# iwing-mrf_shield8.net
KiCad netlist of a schematic drawn in EAGLE
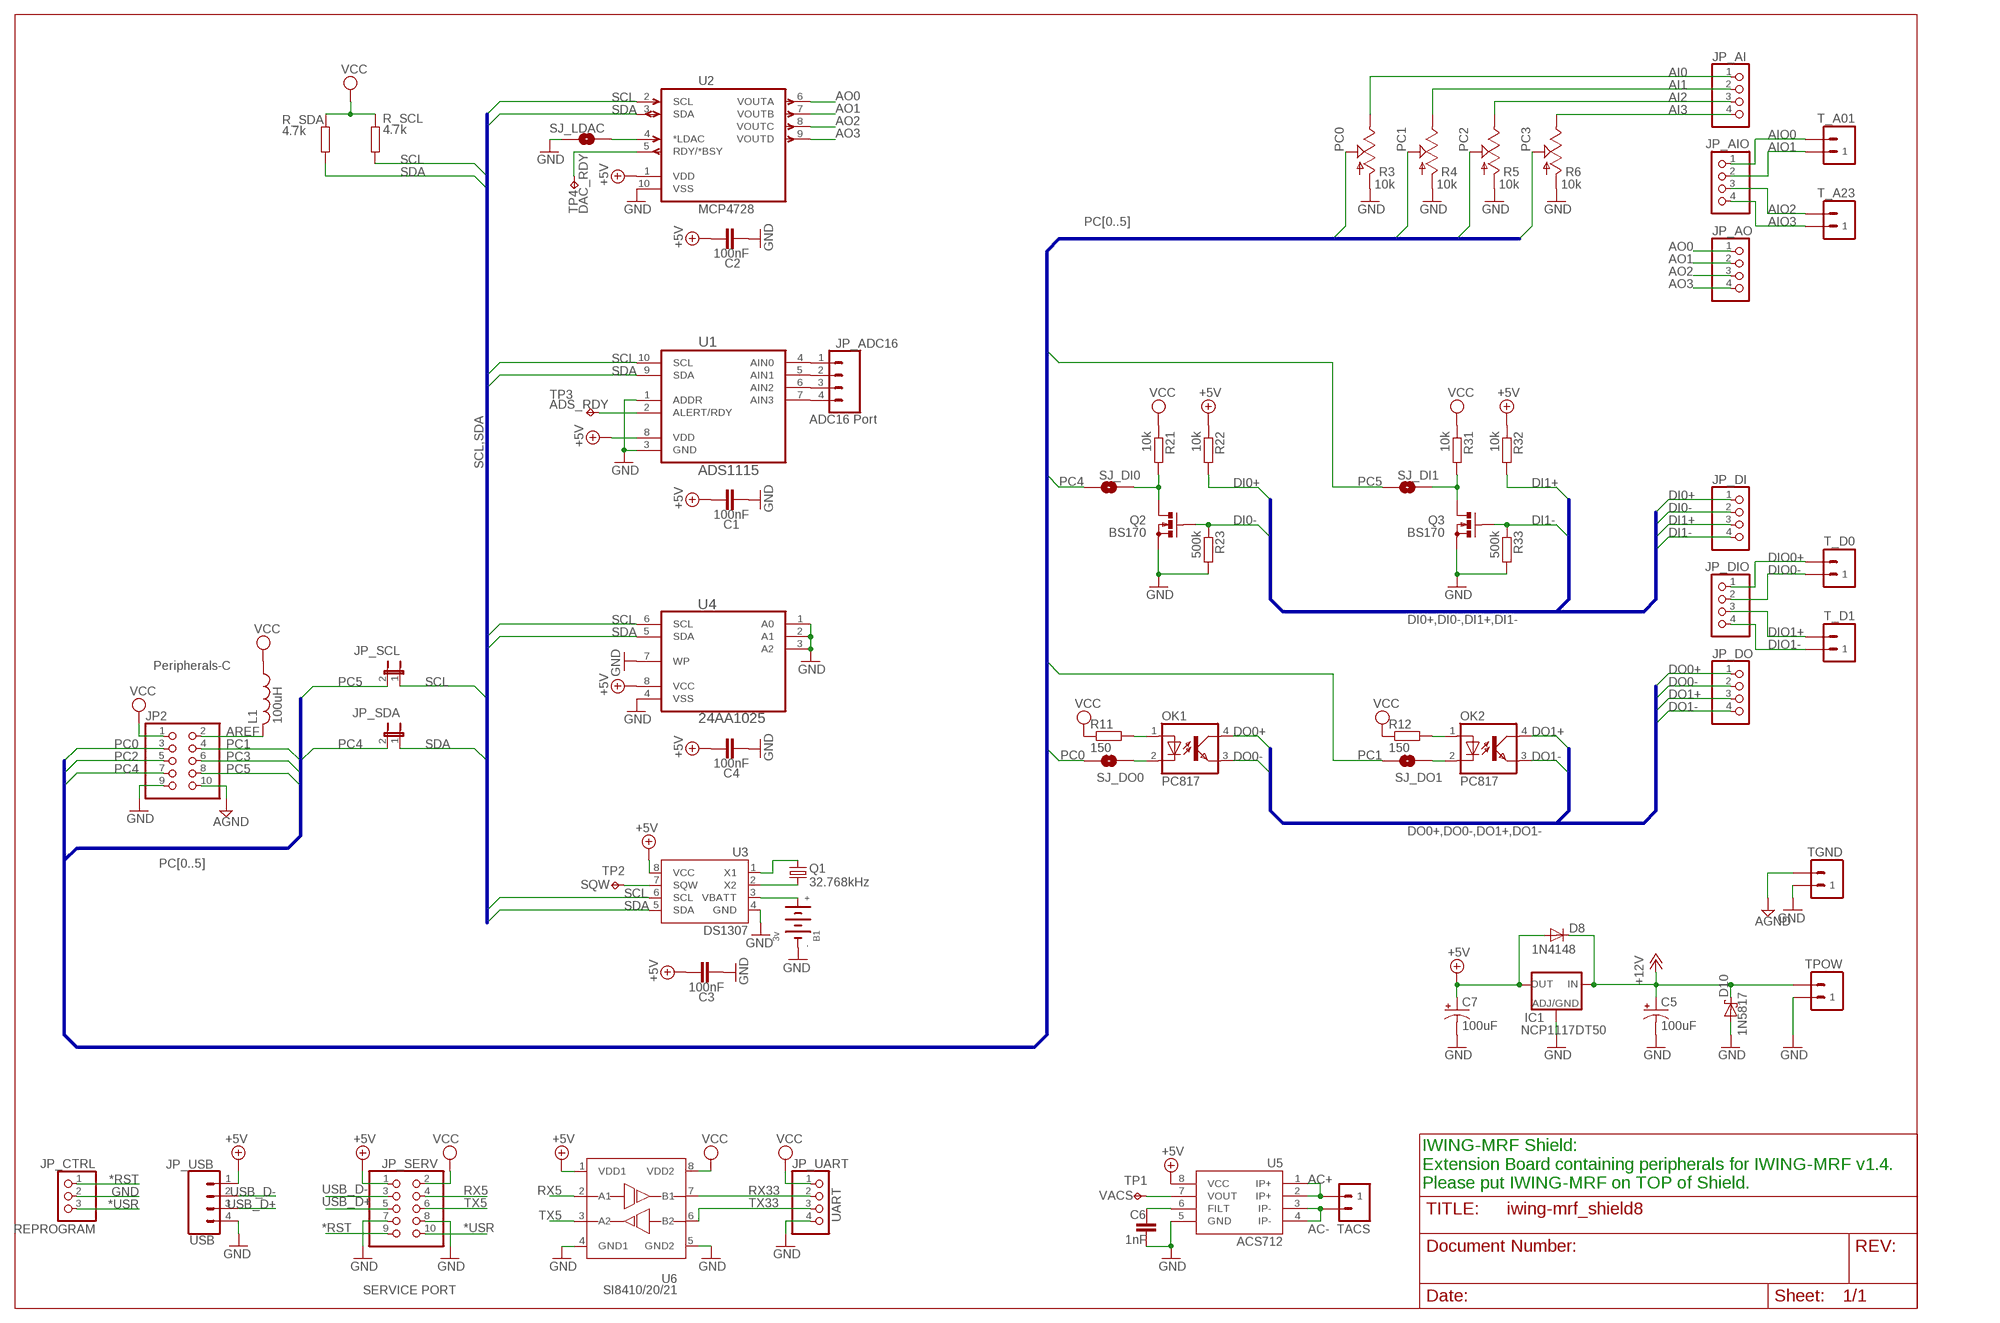
[diagram p0: schematic, sheet 1]

(export (version "E")
  (design (tool "Eeschema 10.0.6"))
  (components
    (comp (ref "B1")
      (value "3v")
      (footprint "eagle-import:CR2032")
      (libsource (lib "eagle-import") (part "BATTERYCR2032"))
    )
    (comp (ref "C1")
      (value "100nF")
      (footprint "eagle-import:RCL_C050-025X075")
      (libsource (lib "eagle-import") (part "RCL_C-EU050-025X075"))
    )
    (comp (ref "C2")
      (value "100nF")
      (footprint "eagle-import:RCL_C050-025X075")
      (libsource (lib "eagle-import") (part "RCL_C-EU050-025X075"))
    )
    (comp (ref "C3")
      (value "100nF")
      (footprint "eagle-import:RCL_C050-025X075")
      (libsource (lib "eagle-import") (part "RCL_C-EU050-025X075"))
    )
    (comp (ref "C4")
      (value "100nF")
      (footprint "eagle-import:RCL_C050-025X075")
      (libsource (lib "eagle-import") (part "RCL_C-EU050-025X075"))
    )
    (comp (ref "C5")
      (value "100uF")
      (footprint "eagle-import:RCL_E2,5-7")
      (libsource (lib "eagle-import") (part "RCL_CPOL-USE2.5-7"))
    )
    (comp (ref "C6")
      (value "1nF")
      (footprint "eagle-import:RCL_C050-025X075")
      (libsource (lib "eagle-import") (part "RCL_C-EU050-025X075"))
    )
    (comp (ref "C7")
      (value "100uF")
      (footprint "eagle-import:RCL_E2,5-7")
      (libsource (lib "eagle-import") (part "RCL_CPOL-USE2.5-7"))
    )
    (comp (ref "D8")
      (value "1N4148")
      (footprint "eagle-import:DO35-100V")
      (libsource (lib "eagle-import") (part "1N4148-V"))
    )
    (comp (ref "D10")
      (value "1N5817")
      (footprint "eagle-import:DO41-150V")
      (libsource (lib "eagle-import") (part "1N5819-V"))
    )
    (comp (ref "IC1")
      (value "NCP1117DT50")
      (footprint "eagle-import:DPACK")
      (libsource (lib "eagle-import") (part "NCP1117?DT50"))
    )
    (comp (ref "JP2")
      (value "HEADER-2X5")
      (footprint "eagle-import:2X05")
      (libsource (lib "eagle-import") (part "HEADER-2X5"))
    )
    (comp (ref "JP_ADC16")
      (value "ADC16 Port")
      (footprint "eagle-import:1X04")
      (libsource (lib "eagle-import") (part "M04PTH"))
    )
    (comp (ref "JP_AI")
      (value "HEADER-1X4ROUND")
      (footprint "eagle-import:1X04_ROUND")
      (libsource (lib "eagle-import") (part "HEADER-1X4ROUND"))
    )
    (comp (ref "JP_AIO")
      (value "HEADER-1X4ROUND")
      (footprint "eagle-import:1X04_ROUND")
      (libsource (lib "eagle-import") (part "HEADER-1X4ROUND"))
    )
    (comp (ref "JP_AO")
      (value "HEADER-1X4ROUND")
      (footprint "eagle-import:1X04_ROUND")
      (libsource (lib "eagle-import") (part "HEADER-1X4ROUND"))
    )
    (comp (ref "JP_CTRL")
      (value "REPROGRAM")
      (footprint "eagle-import:1X03")
      (libsource (lib "eagle-import") (part "PINHD-1X3"))
    )
    (comp (ref "JP_DI")
      (value "HEADER-1X4ROUND")
      (footprint "eagle-import:1X04_ROUND")
      (libsource (lib "eagle-import") (part "HEADER-1X4ROUND"))
    )
    (comp (ref "JP_DIO")
      (value "HEADER-1X4ROUND")
      (footprint "eagle-import:1X04_ROUND")
      (libsource (lib "eagle-import") (part "HEADER-1X4ROUND"))
    )
    (comp (ref "JP_DO")
      (value "HEADER-1X4ROUND")
      (footprint "eagle-import:1X04_ROUND")
      (libsource (lib "eagle-import") (part "HEADER-1X4ROUND"))
    )
    (comp (ref "JP_SCL")
      (value "JUMPER-2SMD-NO")
      (footprint "eagle-import:SJ_2S-NO")
      (libsource (lib "eagle-import") (part "JUMPER-2SMD-NO"))
    )
    (comp (ref "JP_SDA")
      (value "JUMPER-2SMD-NO")
      (footprint "eagle-import:SJ_2S-NO")
      (libsource (lib "eagle-import") (part "JUMPER-2SMD-NO"))
    )
    (comp (ref "JP_SERV")
      (value "SERVICE PORT")
      (footprint "eagle-import:2X05")
      (libsource (lib "eagle-import") (part "HEADER-2X5"))
    )
    (comp (ref "JP_UART")
      (value "HEADER-1X4ROUND")
      (footprint "eagle-import:1X04_ROUND")
      (libsource (lib "eagle-import") (part "HEADER-1X4ROUND"))
    )
    (comp (ref "JP_USB")
      (value "USB")
      (footprint "eagle-import:1X04")
      (libsource (lib "eagle-import") (part "M04PTH"))
    )
    (comp (ref "L1")
      (value "100uH")
      (footprint "eagle-import:0204_5")
      (libsource (lib "eagle-import") (part "L-US0204/5"))
    )
    (comp (ref "OK1")
      (value "PC817")
      (footprint "eagle-import:DIL04")
      (fields (field (name "MPN") "PC817X4J000F"))
      (libsource (lib "eagle-import") (part "PC817"))
    )
    (comp (ref "OK2")
      (value "PC817")
      (footprint "eagle-import:DIL04")
      (fields (field (name "MPN") "PC817X4J000F"))
      (libsource (lib "eagle-import") (part "PC817"))
    )
    (comp (ref "Q1")
      (value "32.768kHz")
      (footprint "eagle-import:CRYSTAL_TC26H")
      (libsource (lib "eagle-import") (part "CRYSTAL_CRYSTALTC26H"))
    )
    (comp (ref "Q2")
      (value "BS170")
      (footprint "eagle-import:TO92-")
      (libsource (lib "eagle-import") (part "BS170"))
    )
    (comp (ref "Q3")
      (value "BS170")
      (footprint "eagle-import:TO92-")
      (libsource (lib "eagle-import") (part "BS170"))
    )
    (comp (ref "R3")
      (value "10k")
      (footprint "eagle-import:B64Y")
      (libsource (lib "eagle-import") (part "TRIM_US-B64Y"))
    )
    (comp (ref "R4")
      (value "10k")
      (footprint "eagle-import:B64Y")
      (libsource (lib "eagle-import") (part "TRIM_US-B64Y"))
    )
    (comp (ref "R5")
      (value "10k")
      (footprint "eagle-import:B64Y")
      (libsource (lib "eagle-import") (part "TRIM_US-B64Y"))
    )
    (comp (ref "R6")
      (value "10k")
      (footprint "eagle-import:B64Y")
      (libsource (lib "eagle-import") (part "TRIM_US-B64Y"))
    )
    (comp (ref "R11")
      (value "150")
      (footprint "eagle-import:0204_5")
      (libsource (lib "eagle-import") (part "R-EU_0204/5"))
    )
    (comp (ref "R12")
      (value "150")
      (footprint "eagle-import:0204_5")
      (libsource (lib "eagle-import") (part "R-EU_0204/5"))
    )
    (comp (ref "R21")
      (value "10k")
      (footprint "eagle-import:0204_5")
      (libsource (lib "eagle-import") (part "R-EU_0204/5"))
    )
    (comp (ref "R22")
      (value "10k")
      (footprint "eagle-import:0204_5")
      (libsource (lib "eagle-import") (part "R-EU_0204/5"))
    )
    (comp (ref "R23")
      (value "500k")
      (footprint "eagle-import:0204_5")
      (libsource (lib "eagle-import") (part "R-EU_0204/5"))
    )
    (comp (ref "R31")
      (value "10k")
      (footprint "eagle-import:0204_5")
      (libsource (lib "eagle-import") (part "R-EU_0204/5"))
    )
    (comp (ref "R32")
      (value "10k")
      (footprint "eagle-import:0204_5")
      (libsource (lib "eagle-import") (part "R-EU_0204/5"))
    )
    (comp (ref "R33")
      (value "500k")
      (footprint "eagle-import:0204_5")
      (libsource (lib "eagle-import") (part "R-EU_0204/5"))
    )
    (comp (ref "R_SCL")
      (value "4.7k")
      (footprint "eagle-import:0204_5")
      (libsource (lib "eagle-import") (part "R-EU_0204/5"))
    )
    (comp (ref "R_SDA")
      (value "4.7k")
      (footprint "eagle-import:0204_5")
      (libsource (lib "eagle-import") (part "R-EU_0204/5"))
    )
    (comp (ref "SJ_DI0")
      (value "SOLDERJUMPERNO")
      (footprint "eagle-import:SJ_2S-NO")
      (libsource (lib "eagle-import") (part "SOLDERJUMPERNO"))
    )
    (comp (ref "SJ_DI1")
      (value "SOLDERJUMPERNO")
      (footprint "eagle-import:SJ_2S-NO")
      (libsource (lib "eagle-import") (part "SOLDERJUMPERNO"))
    )
    (comp (ref "SJ_DO0")
      (value "SOLDERJUMPERNO")
      (footprint "eagle-import:SJ_2S-NO")
      (libsource (lib "eagle-import") (part "SOLDERJUMPERNO"))
    )
    (comp (ref "SJ_DO1")
      (value "SOLDERJUMPERNO")
      (footprint "eagle-import:SJ_2S-NO")
      (libsource (lib "eagle-import") (part "SOLDERJUMPERNO"))
    )
    (comp (ref "SJ_LDAC")
      (value "SOLDERJUMPERNO")
      (footprint "eagle-import:SJ_2S-NO")
      (libsource (lib "eagle-import") (part "SOLDERJUMPERNO"))
    )
    (comp (ref "TACS")
      (value "ST02-DT-126")
      (footprint "eagle-import:DT-126VP-2P")
      (libsource (lib "eagle-import") (part "ST02-DT-126"))
    )
    (comp (ref "TGND")
      (value "ST02-5MM")
      (footprint "eagle-import:EK500V-02P")
      (libsource (lib "eagle-import") (part "ST02-5MM"))
    )
    (comp (ref "TP1")
      (value "TPPAD1-13")
      (footprint "eagle-import:P1-13")
      (fields (field (name "TP_SIGNAL_NAME") "VACS"))
      (libsource (lib "eagle-import") (part "TPPAD1-13"))
    )
    (comp (ref "TP2")
      (value "TPPAD1-13")
      (footprint "eagle-import:P1-13")
      (fields (field (name "TP_SIGNAL_NAME") "SQW"))
      (libsource (lib "eagle-import") (part "TPPAD1-13"))
    )
    (comp (ref "TP3")
      (value "TPB1,27")
      (footprint "eagle-import:B1,27")
      (fields (field (name "TP_SIGNAL_NAME") "ADS_RDY"))
      (libsource (lib "eagle-import") (part "TPB1,27"))
    )
    (comp (ref "TP4")
      (value "TPPAD1-13")
      (footprint "eagle-import:P1-13")
      (fields (field (name "TP_SIGNAL_NAME") "DAC_RDY"))
      (libsource (lib "eagle-import") (part "TPPAD1-13"))
    )
    (comp (ref "TPOW")
      (value "ST02-5MM")
      (footprint "eagle-import:EK500V-02P")
      (libsource (lib "eagle-import") (part "ST02-5MM"))
    )
    (comp (ref "T_A01")
      (value "ST02-5MM")
      (footprint "eagle-import:EK500V-02P")
      (libsource (lib "eagle-import") (part "ST02-5MM"))
    )
    (comp (ref "T_A23")
      (value "ST02-5MM")
      (footprint "eagle-import:EK500V-02P")
      (libsource (lib "eagle-import") (part "ST02-5MM"))
    )
    (comp (ref "T_D0")
      (value "ST02-5MM")
      (footprint "eagle-import:EK500V-02P")
      (libsource (lib "eagle-import") (part "ST02-5MM"))
    )
    (comp (ref "T_D1")
      (value "ST02-5MM")
      (footprint "eagle-import:EK500V-02P")
      (libsource (lib "eagle-import") (part "ST02-5MM"))
    )
    (comp (ref "U1")
      (value "ADS1115")
      (footprint "eagle-import:MSOP-10")
      (libsource (lib "eagle-import") (part "ADS1115IDGST"))
    )
    (comp (ref "U2")
      (value "MCP4728")
      (footprint "eagle-import:MSOP-10")
      (libsource (lib "eagle-import") (part "MCP4728-E/UN"))
    )
    (comp (ref "U3")
      (value "DS1307")
      (footprint "eagle-import:DIL08")
      (libsource (lib "eagle-import") (part "DS1307D08"))
    )
    (comp (ref "U4")
      (value "24AA1025")
      (footprint "eagle-import:DIL08")
      (libsource (lib "eagle-import") (part "24AA1025-I/P"))
    )
    (comp (ref "U5")
      (value "ACS712")
      (footprint "eagle-import:SO08")
      (libsource (lib "eagle-import") (part "ACS712"))
    )
    (comp (ref "U6")
      (value "SI8410/20/21")
      (footprint "eagle-import:SO-08")
      (libsource (lib "eagle-import") (part "SI8410/20/21"))
    )
  )
  (nets
    (net (code "1") (name "+5V") (class "Default")
      (node (ref "C1") (pin "1") (pinfunction "1_1") (pintype "passive"))
      (node (ref "C2") (pin "1") (pinfunction "1_1") (pintype "passive"))
      (node (ref "C3") (pin "1") (pinfunction "1_1") (pintype "passive"))
      (node (ref "C4") (pin "1") (pinfunction "1_1") (pintype "passive"))
      (node (ref "C7") (pin "+") (pinfunction "+_+") (pintype "passive"))
      (node (ref "D8") (pin "A") (pinfunction "A_A") (pintype "passive"))
      (node (ref "IC1") (pin "4") (pinfunction "OUT_4") (pintype "passive"))
      (node (ref "JP_SERV") (pin "1") (pinfunction "1_1") (pintype "passive"))
      (node (ref "JP_USB") (pin "1") (pinfunction "1_1") (pintype "passive"))
      (node (ref "R22") (pin "1") (pinfunction "1_1") (pintype "passive"))
      (node (ref "R32") (pin "1") (pinfunction "1_1") (pintype "passive"))
      (node (ref "U1") (pin "8") (pinfunction "VDD_8") (pintype "power_in"))
      (node (ref "U2") (pin "1") (pinfunction "VDD_1") (pintype "power_in"))
      (node (ref "U3") (pin "8") (pinfunction "VCC_8") (pintype "bidirectional"))
      (node (ref "U4") (pin "8") (pinfunction "VCC_8") (pintype "power_in"))
      (node (ref "U5") (pin "8") (pinfunction "VCC_8") (pintype "bidirectional"))
      (node (ref "U6") (pin "1") (pinfunction "VDD1_1") (pintype "power_in"))
    )
    (net (code "2") (name "+12V") (class "Default")
      (node (ref "C5") (pin "+") (pinfunction "+_+") (pintype "passive"))
      (node (ref "D10") (pin "C") (pinfunction "C_C") (pintype "passive"))
      (node (ref "D8") (pin "C") (pinfunction "C_C") (pintype "passive"))
      (node (ref "IC1") (pin "3") (pinfunction "IN_3") (pintype "input"))
      (node (ref "TPOW") (pin "P$2") (pinfunction "2_P$2") (pintype "passive"))
    )
    (net (code "3") (name "/*RST") (class "Default")
      (node (ref "JP_CTRL") (pin "1") (pinfunction "1_1") (pintype "passive"))
      (node (ref "JP_SERV") (pin "9") (pinfunction "9_9") (pintype "passive"))
    )
    (net (code "4") (name "/*USR") (class "Default")
      (node (ref "JP_CTRL") (pin "3") (pinfunction "3_3") (pintype "passive"))
      (node (ref "JP_SERV") (pin "10") (pinfunction "10_10") (pintype "passive"))
    )
    (net (code "5") (name "/AC+") (class "Default")
      (node (ref "TACS") (pin "P$1") (pinfunction "1_P$1") (pintype "passive"))
      (node (ref "U5") (pin "1") (pinfunction "IP+_1") (pintype "bidirectional"))
      (node (ref "U5") (pin "2") (pinfunction "IP+_2") (pintype "bidirectional"))
    )
    (net (code "6") (name "/AC-") (class "Default")
      (node (ref "TACS") (pin "P$2") (pinfunction "2_P$2") (pintype "passive"))
      (node (ref "U5") (pin "3") (pinfunction "IP-_3") (pintype "bidirectional"))
      (node (ref "U5") (pin "4") (pinfunction "IP-_4") (pintype "bidirectional"))
    )
    (net (code "7") (name "/AI0") (class "Default")
      (node (ref "JP_AI") (pin "1") (pinfunction "1_1") (pintype "passive"))
      (node (ref "R3") (pin "E") (pinfunction "E_E") (pintype "passive"))
    )
    (net (code "8") (name "/AI1") (class "Default")
      (node (ref "JP_AI") (pin "2") (pinfunction "2_2") (pintype "passive"))
      (node (ref "R4") (pin "E") (pinfunction "E_E") (pintype "passive"))
    )
    (net (code "9") (name "/AI2") (class "Default")
      (node (ref "JP_AI") (pin "3") (pinfunction "3_3") (pintype "passive"))
      (node (ref "R5") (pin "E") (pinfunction "E_E") (pintype "passive"))
    )
    (net (code "10") (name "/AI3") (class "Default")
      (node (ref "JP_AI") (pin "4") (pinfunction "4_4") (pintype "passive"))
      (node (ref "R6") (pin "E") (pinfunction "E_E") (pintype "passive"))
    )
    (net (code "11") (name "/AIO0") (class "Default")
      (node (ref "JP_AIO") (pin "1") (pinfunction "1_1") (pintype "passive"))
      (node (ref "T_A01") (pin "P$2") (pinfunction "2_P$2") (pintype "passive"))
    )
    (net (code "12") (name "/AIO1") (class "Default")
      (node (ref "JP_AIO") (pin "2") (pinfunction "2_2") (pintype "passive"))
      (node (ref "T_A01") (pin "P$1") (pinfunction "1_P$1") (pintype "passive"))
    )
    (net (code "13") (name "/AIO2") (class "Default")
      (node (ref "JP_AIO") (pin "3") (pinfunction "3_3") (pintype "passive"))
      (node (ref "T_A23") (pin "P$2") (pinfunction "2_P$2") (pintype "passive"))
    )
    (net (code "14") (name "/AIO3") (class "Default")
      (node (ref "JP_AIO") (pin "4") (pinfunction "4_4") (pintype "passive"))
      (node (ref "T_A23") (pin "P$1") (pinfunction "1_P$1") (pintype "passive"))
    )
    (net (code "15") (name "/AO0") (class "Default")
      (node (ref "JP_AO") (pin "1") (pinfunction "1_1") (pintype "passive"))
      (node (ref "U2") (pin "6") (pinfunction "VOUTA_6") (pintype "output"))
    )
    (net (code "16") (name "/AO1") (class "Default")
      (node (ref "JP_AO") (pin "2") (pinfunction "2_2") (pintype "passive"))
      (node (ref "U2") (pin "7") (pinfunction "VOUTB_7") (pintype "output"))
    )
    (net (code "17") (name "/AO2") (class "Default")
      (node (ref "JP_AO") (pin "3") (pinfunction "3_3") (pintype "passive"))
      (node (ref "U2") (pin "8") (pinfunction "VOUTC_8") (pintype "output"))
    )
    (net (code "18") (name "/AO3") (class "Default")
      (node (ref "JP_AO") (pin "4") (pinfunction "4_4") (pintype "passive"))
      (node (ref "U2") (pin "9") (pinfunction "VOUTD_9") (pintype "output"))
    )
    (net (code "19") (name "/AREF") (class "Default")
      (node (ref "JP2") (pin "2") (pinfunction "2_2") (pintype "passive"))
      (node (ref "L1") (pin "2") (pinfunction "2_2") (pintype "passive"))
    )
    (net (code "20") (name "/DI0+") (class "Default")
      (node (ref "JP_DI") (pin "1") (pinfunction "1_1") (pintype "passive"))
      (node (ref "R22") (pin "2") (pinfunction "2_2") (pintype "passive"))
    )
    (net (code "21") (name "/DI0-") (class "Default")
      (node (ref "JP_DI") (pin "2") (pinfunction "2_2") (pintype "passive"))
      (node (ref "Q2") (pin "2") (pinfunction "G_2") (pintype "passive"))
      (node (ref "R23") (pin "1") (pinfunction "1_1") (pintype "passive"))
    )
    (net (code "22") (name "/DI1+") (class "Default")
      (node (ref "JP_DI") (pin "3") (pinfunction "3_3") (pintype "passive"))
      (node (ref "R32") (pin "2") (pinfunction "2_2") (pintype "passive"))
    )
    (net (code "23") (name "/DI1-") (class "Default")
      (node (ref "JP_DI") (pin "4") (pinfunction "4_4") (pintype "passive"))
      (node (ref "Q3") (pin "2") (pinfunction "G_2") (pintype "passive"))
      (node (ref "R33") (pin "1") (pinfunction "1_1") (pintype "passive"))
    )
    (net (code "24") (name "/DIO0+") (class "Default")
      (node (ref "JP_DIO") (pin "1") (pinfunction "1_1") (pintype "passive"))
      (node (ref "T_D0") (pin "P$2") (pinfunction "2_P$2") (pintype "passive"))
    )
    (net (code "25") (name "/DIO0-") (class "Default")
      (node (ref "JP_DIO") (pin "2") (pinfunction "2_2") (pintype "passive"))
      (node (ref "T_D0") (pin "P$1") (pinfunction "1_P$1") (pintype "passive"))
    )
    (net (code "26") (name "/DIO1+") (class "Default")
      (node (ref "JP_DIO") (pin "3") (pinfunction "3_3") (pintype "passive"))
      (node (ref "T_D1") (pin "P$2") (pinfunction "2_P$2") (pintype "passive"))
    )
    (net (code "27") (name "/DIO1-") (class "Default")
      (node (ref "JP_DIO") (pin "4") (pinfunction "4_4") (pintype "passive"))
      (node (ref "T_D1") (pin "P$1") (pinfunction "1_P$1") (pintype "passive"))
    )
    (net (code "28") (name "/DO0+") (class "Default")
      (node (ref "JP_DO") (pin "1") (pinfunction "1_1") (pintype "passive"))
      (node (ref "OK1") (pin "4") (pinfunction "COL_4") (pintype "passive"))
    )
    (net (code "29") (name "/DO0-") (class "Default")
      (node (ref "JP_DO") (pin "2") (pinfunction "2_2") (pintype "passive"))
      (node (ref "OK1") (pin "3") (pinfunction "EMIT_3") (pintype "passive"))
    )
    (net (code "30") (name "/DO1+") (class "Default")
      (node (ref "JP_DO") (pin "3") (pinfunction "3_3") (pintype "passive"))
      (node (ref "OK2") (pin "4") (pinfunction "COL_4") (pintype "passive"))
    )
    (net (code "31") (name "/DO1-") (class "Default")
      (node (ref "JP_DO") (pin "4") (pinfunction "4_4") (pintype "passive"))
      (node (ref "OK2") (pin "3") (pinfunction "EMIT_3") (pintype "passive"))
    )
    (net (code "32") (name "/PC0") (class "Default")
      (node (ref "JP2") (pin "3") (pinfunction "3_3") (pintype "passive"))
      (node (ref "R3") (pin "S") (pinfunction "S_S") (pintype "passive"))
      (node (ref "SJ_DO0") (pin "1") (pinfunction "1_1") (pintype "passive"))
    )
    (net (code "33") (name "/PC1") (class "Default")
      (node (ref "JP2") (pin "4") (pinfunction "4_4") (pintype "passive"))
      (node (ref "R4") (pin "S") (pinfunction "S_S") (pintype "passive"))
      (node (ref "SJ_DO1") (pin "1") (pinfunction "1_1") (pintype "passive"))
    )
    (net (code "34") (name "/PC2") (class "Default")
      (node (ref "JP2") (pin "5") (pinfunction "5_5") (pintype "passive"))
      (node (ref "R5") (pin "S") (pinfunction "S_S") (pintype "passive"))
    )
    (net (code "35") (name "/PC3") (class "Default")
      (node (ref "JP2") (pin "6") (pinfunction "6_6") (pintype "passive"))
      (node (ref "R6") (pin "S") (pinfunction "S_S") (pintype "passive"))
    )
    (net (code "36") (name "/PC4") (class "Default")
      (node (ref "JP2") (pin "7") (pinfunction "7_7") (pintype "passive"))
      (node (ref "JP_SDA") (pin "2") (pinfunction "2_2") (pintype "passive"))
      (node (ref "SJ_DI0") (pin "2") (pinfunction "2_2") (pintype "passive"))
    )
    (net (code "37") (name "/PC5") (class "Default")
      (node (ref "JP2") (pin "8") (pinfunction "8_8") (pintype "passive"))
      (node (ref "JP_SCL") (pin "2") (pinfunction "2_2") (pintype "passive"))
      (node (ref "SJ_DI1") (pin "2") (pinfunction "2_2") (pintype "passive"))
    )
    (net (code "39") (name "/RX5") (class "Default")
      (node (ref "JP_SERV") (pin "4") (pinfunction "4_4") (pintype "passive"))
      (node (ref "U6") (pin "2") (pinfunction "A1_2") (pintype "input"))
    )
    (net (code "40") (name "/RX33") (class "Default")
      (node (ref "JP_UART") (pin "2") (pinfunction "2_2") (pintype "passive"))
      (node (ref "U6") (pin "7") (pinfunction "B1_7") (pintype "output"))
    )
    (net (code "41") (name "/SCL") (class "Default")
      (node (ref "JP_SCL") (pin "1") (pinfunction "1_1") (pintype "passive"))
      (node (ref "R_SCL") (pin "2") (pinfunction "2_2") (pintype "passive"))
      (node (ref "U1") (pin "10") (pinfunction "SCL_10") (pintype "input"))
      (node (ref "U2") (pin "2") (pinfunction "SCL_2") (pintype "input"))
      (node (ref "U3") (pin "6") (pinfunction "SCL_6") (pintype "bidirectional"))
      (node (ref "U4") (pin "6") (pinfunction "SCL_6") (pintype "input"))
    )
    (net (code "42") (name "/SDA") (class "Default")
      (node (ref "JP_SDA") (pin "1") (pinfunction "1_1") (pintype "passive"))
      (node (ref "R_SDA") (pin "2") (pinfunction "2_2") (pintype "passive"))
      (node (ref "U1") (pin "9") (pinfunction "SDA_9") (pintype "bidirectional"))
      (node (ref "U2") (pin "3") (pinfunction "SDA_3") (pintype "bidirectional"))
      (node (ref "U3") (pin "5") (pinfunction "SDA_5") (pintype "bidirectional"))
      (node (ref "U4") (pin "5") (pinfunction "SDA_5") (pintype "bidirectional"))
    )
    (net (code "43") (name "/TX5") (class "Default")
      (node (ref "JP_SERV") (pin "6") (pinfunction "6_6") (pintype "passive"))
      (node (ref "U6") (pin "3") (pinfunction "A2_3") (pintype "output"))
    )
    (net (code "44") (name "/TX33") (class "Default")
      (node (ref "JP_UART") (pin "3") (pinfunction "3_3") (pintype "passive"))
      (node (ref "U6") (pin "6") (pinfunction "B2_6") (pintype "input"))
    )
    (net (code "45") (name "/USB_D+") (class "Default")
      (node (ref "JP_SERV") (pin "5") (pinfunction "5_5") (pintype "passive"))
      (node (ref "JP_USB") (pin "3") (pinfunction "3_3") (pintype "passive"))
    )
    (net (code "46") (name "/USB_D-") (class "Default")
      (node (ref "JP_SERV") (pin "3") (pinfunction "3_3") (pintype "passive"))
      (node (ref "JP_USB") (pin "2") (pinfunction "2_2") (pintype "passive"))
    )
    (net (code "50") (name "AGND") (class "Default")
      (node (ref "JP2") (pin "10") (pinfunction "10_10") (pintype "passive"))
      (node (ref "TGND") (pin "P$2") (pinfunction "2_P$2") (pintype "passive"))
    )
    (net (code "51") (name "GND") (class "Default")
      (node (ref "B1") (pin "-") (pinfunction "-_-") (pintype "passive"))
      (node (ref "C1") (pin "2") (pinfunction "2_2") (pintype "passive"))
      (node (ref "C2") (pin "2") (pinfunction "2_2") (pintype "passive"))
      (node (ref "C3") (pin "2") (pinfunction "2_2") (pintype "passive"))
      (node (ref "C4") (pin "2") (pinfunction "2_2") (pintype "passive"))
      (node (ref "C5") (pin "-") (pinfunction "-_-") (pintype "passive"))
      (node (ref "C6") (pin "2") (pinfunction "2_2") (pintype "passive"))
      (node (ref "C7") (pin "-") (pinfunction "-_-") (pintype "passive"))
      (node (ref "D10") (pin "A") (pinfunction "A_A") (pintype "passive"))
      (node (ref "IC1") (pin "1") (pinfunction "ADJ_1") (pintype "input"))
      (node (ref "JP2") (pin "9") (pinfunction "9_9") (pintype "passive"))
      (node (ref "JP_CTRL") (pin "2") (pinfunction "2_2") (pintype "passive"))
      (node (ref "JP_SERV") (pin "7") (pinfunction "7_7") (pintype "passive"))
      (node (ref "JP_SERV") (pin "8") (pinfunction "8_8") (pintype "passive"))
      (node (ref "JP_UART") (pin "4") (pinfunction "4_4") (pintype "passive"))
      (node (ref "JP_USB") (pin "4") (pinfunction "4_4") (pintype "passive"))
      (node (ref "Q2") (pin "3") (pinfunction "S_3") (pintype "passive"))
      (node (ref "Q3") (pin "3") (pinfunction "S_3") (pintype "passive"))
      (node (ref "R23") (pin "2") (pinfunction "2_2") (pintype "passive"))
      (node (ref "R3") (pin "A") (pinfunction "A_A") (pintype "passive"))
      (node (ref "R33") (pin "2") (pinfunction "2_2") (pintype "passive"))
      (node (ref "R4") (pin "A") (pinfunction "A_A") (pintype "passive"))
      (node (ref "R5") (pin "A") (pinfunction "A_A") (pintype "passive"))
      (node (ref "R6") (pin "A") (pinfunction "A_A") (pintype "passive"))
      (node (ref "SJ_LDAC") (pin "1") (pinfunction "1_1") (pintype "passive"))
      (node (ref "TGND") (pin "P$1") (pinfunction "1_P$1") (pintype "passive"))
      (node (ref "TPOW") (pin "P$1") (pinfunction "1_P$1") (pintype "passive"))
      (node (ref "U1") (pin "1") (pinfunction "ADDR_1") (pintype "input"))
      (node (ref "U1") (pin "3") (pinfunction "GND_3") (pintype "passive"))
      (node (ref "U2") (pin "10") (pinfunction "VSS_10") (pintype "power_in"))
      (node (ref "U3") (pin "4") (pinfunction "GND_4") (pintype "bidirectional"))
      (node (ref "U4") (pin "1") (pinfunction "A0_1") (pintype "input"))
      (node (ref "U4") (pin "2") (pinfunction "A1_2") (pintype "input"))
      (node (ref "U4") (pin "3") (pinfunction "A2_3") (pintype "input"))
      (node (ref "U4") (pin "4") (pinfunction "VSS_4") (pintype "passive"))
      (node (ref "U4") (pin "7") (pinfunction "WP_7") (pintype "input"))
      (node (ref "U5") (pin "5") (pinfunction "GND_5") (pintype "bidirectional"))
      (node (ref "U6") (pin "4") (pinfunction "GND1_4") (pintype "power_in"))
      (node (ref "U6") (pin "5") (pinfunction "GND2_5") (pintype "power_in"))
    )
    (net (code "52") (name "Net-(OK1-A)") (class "Default")
      (node (ref "OK1") (pin "1") (pinfunction "A_1") (pintype "passive"))
      (node (ref "R11") (pin "2") (pinfunction "2_2") (pintype "passive"))
    )
    (net (code "53") (name "Net-(OK1-C)") (class "Default")
      (node (ref "OK1") (pin "2") (pinfunction "C_2") (pintype "passive"))
      (node (ref "SJ_DO0") (pin "2") (pinfunction "2_2") (pintype "passive"))
    )
    (net (code "54") (name "Net-(OK2-A)") (class "Default")
      (node (ref "OK2") (pin "1") (pinfunction "A_1") (pintype "passive"))
      (node (ref "R12") (pin "2") (pinfunction "2_2") (pintype "passive"))
    )
    (net (code "55") (name "Net-(OK2-C)") (class "Default")
      (node (ref "OK2") (pin "2") (pinfunction "C_2") (pintype "passive"))
      (node (ref "SJ_DO1") (pin "2") (pinfunction "2_2") (pintype "passive"))
    )
    (net (code "56") (name "Net-(Q2-D)") (class "Default")
      (node (ref "Q2") (pin "1") (pinfunction "D_1") (pintype "passive"))
      (node (ref "R21") (pin "2") (pinfunction "2_2") (pintype "passive"))
      (node (ref "SJ_DI0") (pin "1") (pinfunction "1_1") (pintype "passive"))
    )
    (net (code "57") (name "Net-(Q3-D)") (class "Default")
      (node (ref "Q3") (pin "1") (pinfunction "D_1") (pintype "passive"))
      (node (ref "R31") (pin "2") (pinfunction "2_2") (pintype "passive"))
      (node (ref "SJ_DI1") (pin "1") (pinfunction "1_1") (pintype "passive"))
    )
    (net (code "58") (name "Net-(U1-AIN0)") (class "Default")
      (node (ref "JP_ADC16") (pin "1") (pinfunction "1_1") (pintype "passive"))
      (node (ref "U1") (pin "4") (pinfunction "AIN0_4") (pintype "input"))
    )
    (net (code "59") (name "Net-(U1-AIN1)") (class "Default")
      (node (ref "JP_ADC16") (pin "2") (pinfunction "2_2") (pintype "passive"))
      (node (ref "U1") (pin "5") (pinfunction "AIN1_5") (pintype "input"))
    )
    (net (code "60") (name "Net-(U1-AIN2)") (class "Default")
      (node (ref "JP_ADC16") (pin "3") (pinfunction "3_3") (pintype "passive"))
      (node (ref "U1") (pin "6") (pinfunction "AIN2_6") (pintype "input"))
    )
    (net (code "61") (name "Net-(U1-AIN3)") (class "Default")
      (node (ref "JP_ADC16") (pin "4") (pinfunction "4_4") (pintype "passive"))
      (node (ref "U1") (pin "7") (pinfunction "AIN3_7") (pintype "input"))
    )
    (net (code "62") (name "Net-(U1-ALERT{slash}RDY)") (class "Default")
      (node (ref "TP3") (pin "TP") (pinfunction "TP_TP") (pintype "input"))
      (node (ref "U1") (pin "2") (pinfunction "ALERT/RDY_2") (pintype "input"))
    )
    (net (code "63") (name "Net-(U2-*LDAC)") (class "Default")
      (node (ref "SJ_LDAC") (pin "2") (pinfunction "2_2") (pintype "passive"))
      (node (ref "U2") (pin "4") (pinfunction "*LDAC_4") (pintype "input"))
    )
    (net (code "64") (name "Net-(U2-RDY{slash}*BSY)") (class "Default")
      (node (ref "TP4") (pin "TP") (pinfunction "TP_TP") (pintype "input"))
      (node (ref "U2") (pin "5") (pinfunction "RDY/*BSY_5") (pintype "output"))
    )
    (net (code "65") (name "Net-(U3-SQW)") (class "Default")
      (node (ref "TP2") (pin "TP") (pinfunction "TP_TP") (pintype "input"))
      (node (ref "U3") (pin "7") (pinfunction "SQW_7") (pintype "bidirectional"))
    )
    (net (code "66") (name "Net-(U3-VBATT)") (class "Default")
      (node (ref "B1") (pin "+") (pinfunction "+_+") (pintype "passive"))
      (node (ref "U3") (pin "3") (pinfunction "VBATT_3") (pintype "bidirectional"))
    )
    (net (code "67") (name "Net-(U3-X1)") (class "Default")
      (node (ref "Q1") (pin "2") (pinfunction "2_2") (pintype "passive"))
      (node (ref "U3") (pin "1") (pinfunction "X1_1") (pintype "bidirectional"))
    )
    (net (code "68") (name "Net-(U3-X2)") (class "Default")
      (node (ref "Q1") (pin "1") (pinfunction "1_1") (pintype "passive"))
      (node (ref "U3") (pin "2") (pinfunction "X2_2") (pintype "bidirectional"))
    )
    (net (code "69") (name "Net-(U5-FILT)") (class "Default")
      (node (ref "C6") (pin "1") (pinfunction "1_1") (pintype "passive"))
      (node (ref "U5") (pin "6") (pinfunction "FILT_6") (pintype "bidirectional"))
    )
    (net (code "70") (name "Net-(U5-VOUT)") (class "Default")
      (node (ref "TP1") (pin "TP") (pinfunction "TP_TP") (pintype "input"))
      (node (ref "U5") (pin "7") (pinfunction "VOUT_7") (pintype "bidirectional"))
    )
    (net (code "71") (name "VCC") (class "Default")
      (node (ref "JP2") (pin "1") (pinfunction "1_1") (pintype "passive"))
      (node (ref "JP_SERV") (pin "2") (pinfunction "2_2") (pintype "passive"))
      (node (ref "JP_UART") (pin "1") (pinfunction "1_1") (pintype "passive"))
      (node (ref "L1") (pin "1") (pinfunction "1_1") (pintype "passive"))
      (node (ref "R11") (pin "1") (pinfunction "1_1") (pintype "passive"))
      (node (ref "R12") (pin "1") (pinfunction "1_1") (pintype "passive"))
      (node (ref "R21") (pin "1") (pinfunction "1_1") (pintype "passive"))
      (node (ref "R31") (pin "1") (pinfunction "1_1") (pintype "passive"))
      (node (ref "R_SCL") (pin "1") (pinfunction "1_1") (pintype "passive"))
      (node (ref "R_SDA") (pin "1") (pinfunction "1_1") (pintype "passive"))
      (node (ref "U6") (pin "8") (pinfunction "VDD2_8") (pintype "power_in"))
    )
  )
)
